# design.net
KiCad netlist of a schematic drawn in Altium Designer
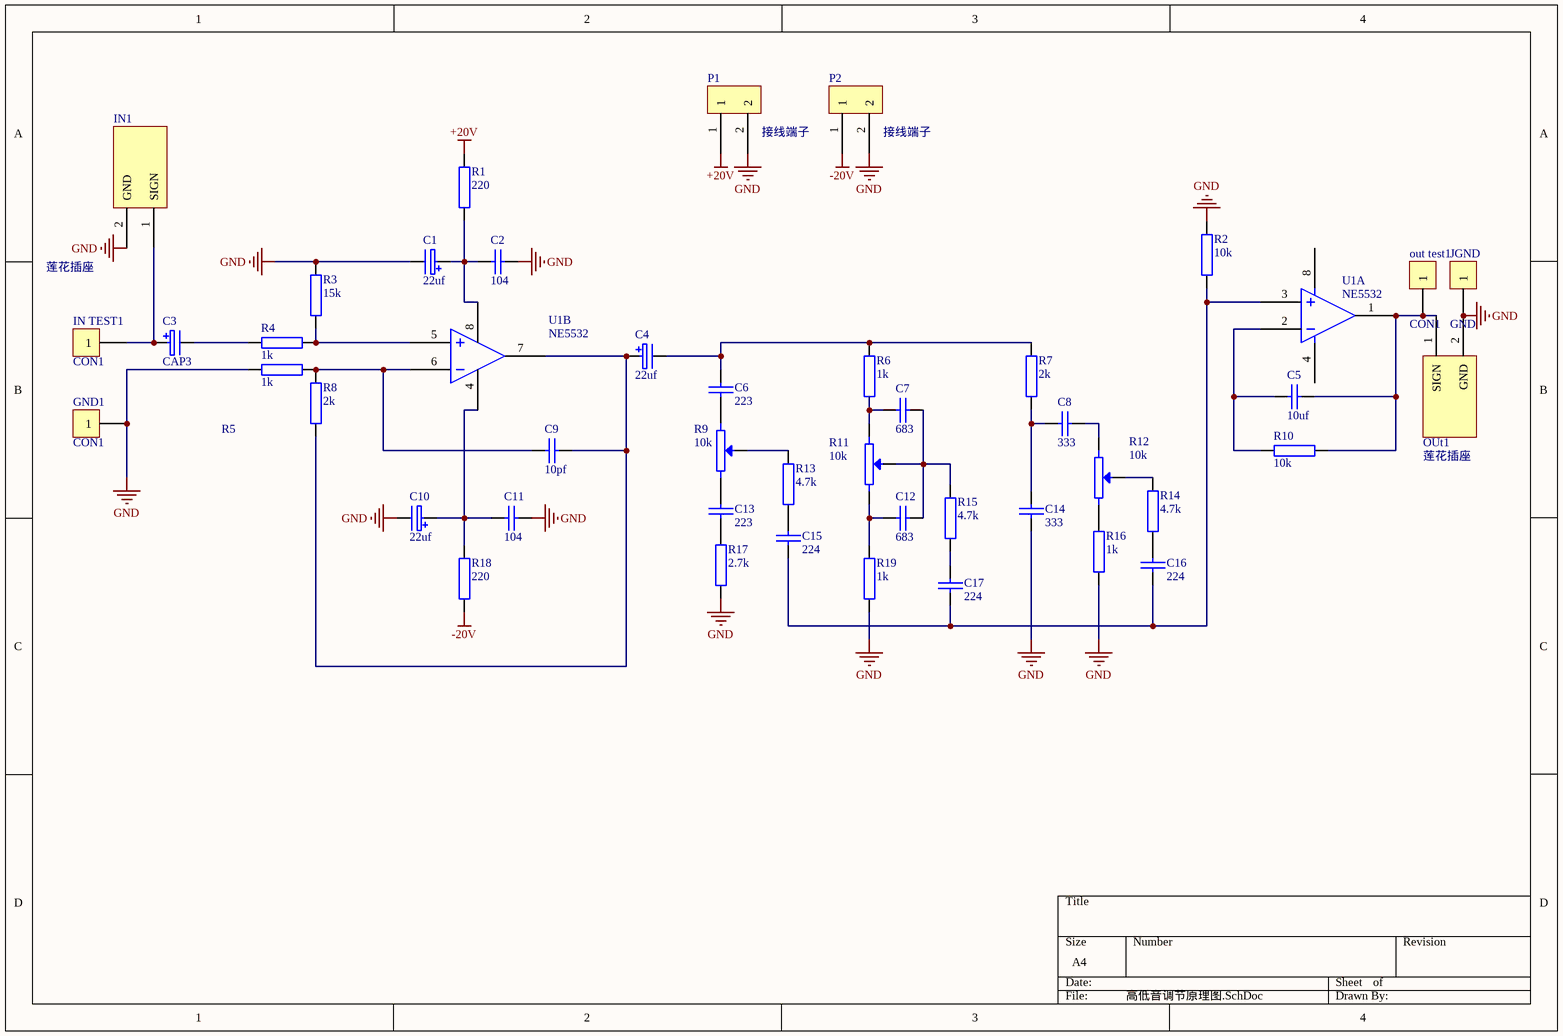
[diagram p0: 高低音调节原理图.SchDoc]

(export (version "E")
  (design (tool "Eeschema 10.0.6"))
  (components
    (comp (ref "C1") (value "22uf") (footprint "CAO2") (libsource (lib "电容") (part "CAP3")))
    (comp (ref "C2") (value "104") (footprint "CAP2") (libsource (lib "电容") (part "CAP1")))
    (comp (ref "C3") (value "CAP3") (footprint "CAO2") (libsource (lib "电容") (part "CAP3")))
    (comp (ref "C4") (value "22uf") (footprint "CAO2") (libsource (lib "电容") (part "CAP3")))
    (comp (ref "C5") (value "10uf") (footprint "CAP2") (libsource (lib "C电容") (part "CAP1")))
    (comp (ref "C6") (value "223") (footprint "CAP2") (libsource (lib "电容") (part "CAP1")))
    (comp (ref "C7") (value "683") (footprint "CAP2") (libsource (lib "电容") (part "CAP1")))
    (comp (ref "C8") (value "333") (footprint "CAP2") (libsource (lib "电容") (part "CAP1")))
    (comp (ref "C9") (value "10pf") (footprint "CAP2") (libsource (lib "电容") (part "CAP1")))
    (comp (ref "C10") (value "22uf") (footprint "CAO2") (libsource (lib "电容") (part "CAP3")))
    (comp (ref "C11") (value "104") (footprint "CAP2") (libsource (lib "电容") (part "CAP1")))
    (comp (ref "C12") (value "683") (footprint "CAP2") (libsource (lib "电容") (part "CAP1")))
    (comp (ref "C13") (value "223") (footprint "CAP2") (libsource (lib "电容") (part "CAP1")))
    (comp (ref "C14") (value "333") (footprint "CAP2") (libsource (lib "电容") (part "CAP1")))
    (comp (ref "C15") (value "224") (footprint "CAP2") (libsource (lib "电容") (part "CAP1")))
    (comp (ref "C16") (value "224") (footprint "CAP2") (libsource (lib "电容") (part "CAP1")))
    (comp (ref "C17") (value "224") (footprint "CAP2") (libsource (lib "电容") (part "CAP1")))
    (comp (ref "GND1")
      (value "CON1")
      (footprint "SIP-1")
      (description "Connector")
      (libsource (lib "排针") (part "CON1"))
    )
    (comp (ref "IN TEST1")
      (value "CON1")
      (footprint "SIP-1")
      (description "Connector")
      (libsource (lib "排针") (part "CON1"))
    )
    (comp (ref "IN1") (value "莲花插座") (footprint "莲花母座") (libsource (lib "音频功放自画库") (part "PCA")))
    (comp (ref "JGND")
      (value "GND")
      (footprint "SIP-1")
      (description "Connector")
      (libsource (lib "") (part "CON1_1"))
    )
    (comp (ref "out test1")
      (value "CON1")
      (footprint "SIP-1")
      (description "Connector")
      (libsource (lib "接口") (part "CON1"))
    )
    (comp (ref "OUt1") (value "莲花插座") (footprint "莲花母座") (libsource (lib "") (part "PCA_1")))
    (comp (ref "P1") (value "接线端子") (footprint "音频功放自画库:接线端子") (libsource (lib "音频功放自画库") (part "接线端子")))
    (comp (ref "P2") (value "接线端子") (footprint "音频功放自画库:接线端子") (libsource (lib "音频功放自画库") (part "接线端子")))
    (comp (ref "R1")
      (value "220")
      (footprint "AXIAL0.4")
      (description "电阻")
      (libsource (lib "电阻") (part "RES"))
    )
    (comp (ref "R2") (value "10k") (footprint "AXIAL0.4") (libsource (lib "R电阻") (part "RES")))
    (comp (ref "R3")
      (value "15k")
      (footprint "AXIAL0.4")
      (description "电阻")
      (libsource (lib "电阻") (part "RES"))
    )
    (comp (ref "R4")
      (value "1k")
      (footprint "AXIAL0.4")
      (description "电阻")
      (libsource (lib "电阻") (part "RES"))
    )
    (comp (ref "R5")
      (value "1k")
      (footprint "AXIAL0.4")
      (description "电阻")
      (libsource (lib "电阻") (part "RES"))
    )
    (comp (ref "R6") (value "1k") (footprint "AXIAL0.4") (libsource (lib "R电阻") (part "RES")))
    (comp (ref "R7") (value "2k") (footprint "AXIAL0.4") (libsource (lib "R电阻") (part "RES")))
    (comp (ref "R8")
      (value "2k")
      (footprint "AXIAL0.4")
      (description "电阻")
      (libsource (lib "电阻") (part "RES"))
    )
    (comp (ref "R9")
      (value "10k")
      (footprint "RVR-A")
      (description "Potentiometer")
      (libsource (lib "R电阻") (part "RPOT-1"))
    )
    (comp (ref "R10") (value "10k") (footprint "AXIAL0.4") (libsource (lib "R电阻") (part "RES")))
    (comp (ref "R11")
      (value "10k")
      (footprint "RVR-A")
      (description "Potentiometer")
      (libsource (lib "R电阻") (part "RPOT-1"))
    )
    (comp (ref "R12")
      (value "10k")
      (footprint "RVR-A")
      (description "Potentiometer")
      (libsource (lib "R电阻") (part "RPOT-1"))
    )
    (comp (ref "R13")
      (value "4.7k")
      (footprint "AXIAL0.4")
      (description "电阻")
      (libsource (lib "电阻") (part "RES"))
    )
    (comp (ref "R14") (value "4.7k") (footprint "AXIAL0.4") (libsource (lib "R电阻") (part "RES")))
    (comp (ref "R15") (value "4.7k") (footprint "AXIAL0.4") (libsource (lib "R电阻") (part "RES")))
    (comp (ref "R16") (value "1k") (footprint "AXIAL0.4") (libsource (lib "R电阻") (part "RES")))
    (comp (ref "R17")
      (value "2.7k")
      (footprint "AXIAL0.4")
      (description "电阻")
      (libsource (lib "电阻") (part "RES"))
    )
    (comp (ref "R18")
      (value "220")
      (footprint "AXIAL0.4")
      (description "电阻")
      (libsource (lib "电阻") (part "RES"))
    )
    (comp (ref "R19")
      (value "1k")
      (footprint "AXIAL0.4")
      (description "电阻")
      (libsource (lib "电阻") (part "RES"))
    )
    (comp (ref "U1") (value "NE5532") (footprint "DIP-8") (libsource (lib "Operational 运放") (part "1458")))
  )
  (nets
    (net (code "1") (name "+20V") (class "Default")
      (node (ref "P1") (pin "1") (pinfunction "1_1") (pintype "passive"))
      (node (ref "R1") (pin "2") (pinfunction "2_2") (pintype "passive"))
    )
    (net (code "2") (name "-20V") (class "Default")
      (node (ref "P2") (pin "1") (pinfunction "1_1") (pintype "passive"))
      (node (ref "R18") (pin "1") (pinfunction "1_1") (pintype "passive"))
    )
    (net (code "3") (name "GND") (class "Default")
      (node (ref "C1") (pin "2") (pintype "passive"))
      (node (ref "C10") (pin "2") (pintype "passive"))
      (node (ref "C11") (pin "1") (pinfunction "1_1") (pintype "passive"))
      (node (ref "C14") (pin "2") (pinfunction "2_2") (pintype "passive"))
      (node (ref "C2") (pin "1") (pinfunction "1_1") (pintype "passive"))
      (node (ref "GND1") (pin "1") (pinfunction "1_1") (pintype "passive"))
      (node (ref "IN1") (pin "2") (pinfunction "GND_2") (pintype "passive"))
      (node (ref "JGND") (pin "1") (pinfunction "1_1") (pintype "passive"))
      (node (ref "OUt1") (pin "2") (pinfunction "GND_2") (pintype "passive"))
      (node (ref "P1") (pin "2") (pinfunction "2_2") (pintype "passive"))
      (node (ref "P2") (pin "2") (pinfunction "2_2") (pintype "passive"))
      (node (ref "R16") (pin "1") (pinfunction "1_1") (pintype "passive"))
      (node (ref "R17") (pin "1") (pinfunction "1_1") (pintype "passive"))
      (node (ref "R19") (pin "1") (pinfunction "1_1") (pintype "passive"))
      (node (ref "R2") (pin "2") (pinfunction "2_2") (pintype "passive"))
      (node (ref "R3") (pin "2") (pinfunction "2_2") (pintype "passive"))
      (node (ref "R5") (pin "1") (pinfunction "1_1") (pintype "passive"))
    )
    (net (code "4") (name "Net-(C1-Pad1)") (class "Default")
      (node (ref "C1") (pin "1") (pintype "passive"))
      (node (ref "C2") (pin "2") (pinfunction "2_2") (pintype "passive"))
      (node (ref "R1") (pin "1") (pinfunction "1_1") (pintype "passive"))
      (node (ref "U1") (pin "8") (pinfunction "8_8") (pintype "passive"))
    )
    (net (code "5") (name "Net-(C3-Pad2)") (class "Default")
      (node (ref "C3") (pin "2") (pintype "passive"))
      (node (ref "R4") (pin "1") (pinfunction "1_1") (pintype "passive"))
    )
    (net (code "6") (name "Net-(C4-Pad1)") (class "Default")
      (node (ref "C4") (pin "1") (pintype "passive"))
      (node (ref "C9") (pin "1") (pinfunction "1_1") (pintype "passive"))
      (node (ref "R8") (pin "1") (pinfunction "1_1") (pintype "passive"))
      (node (ref "U1") (pin "7") (pintype "passive"))
    )
    (net (code "7") (name "Net-(C4-Pad2)") (class "Default")
      (node (ref "C4") (pin "2") (pintype "passive"))
      (node (ref "C6") (pin "1") (pinfunction "1_1") (pintype "passive"))
      (node (ref "R6") (pin "2") (pinfunction "2_2") (pintype "passive"))
      (node (ref "R7") (pin "2") (pinfunction "2_2") (pintype "passive"))
    )
    (net (code "8") (name "Net-(C5-Pad2)") (class "Default")
      (node (ref "C5") (pin "2") (pinfunction "2_2") (pintype "passive"))
      (node (ref "R10") (pin "1") (pinfunction "1_1") (pintype "passive"))
      (node (ref "U1") (pin "2") (pintype "passive"))
    )
    (net (code "9") (name "Net-(C6-Pad2)") (class "Default")
      (node (ref "C6") (pin "2") (pinfunction "2_2") (pintype "passive"))
      (node (ref "R9") (pin "1") (pinfunction "1_1") (pintype "passive"))
    )
    (net (code "10") (name "Net-(C7-Pad2)") (class "Default")
      (node (ref "C7") (pin "2") (pinfunction "2_2") (pintype "passive"))
      (node (ref "R11") (pin "1") (pinfunction "1_1") (pintype "passive"))
      (node (ref "R6") (pin "1") (pinfunction "1_1") (pintype "passive"))
    )
    (net (code "11") (name "Net-(C8-Pad1)") (class "Default")
      (node (ref "C8") (pin "1") (pinfunction "1_1") (pintype "passive"))
      (node (ref "R12") (pin "1") (pinfunction "1_1") (pintype "passive"))
    )
    (net (code "12") (name "Net-(C9-Pad2)") (class "Default")
      (node (ref "C9") (pin "2") (pinfunction "2_2") (pintype "passive"))
      (node (ref "R5") (pin "2") (pinfunction "2_2") (pintype "passive"))
      (node (ref "R8") (pin "2") (pinfunction "2_2") (pintype "passive"))
      (node (ref "U1") (pin "6") (pintype "passive"))
    )
    (net (code "13") (name "Net-(C10-Pad1)") (class "Default")
      (node (ref "C10") (pin "1") (pintype "passive"))
      (node (ref "C11") (pin "2") (pinfunction "2_2") (pintype "passive"))
      (node (ref "R18") (pin "2") (pinfunction "2_2") (pintype "passive"))
      (node (ref "U1") (pin "4") (pinfunction "4_4") (pintype "passive"))
    )
    (net (code "14") (name "Net-(C12-Pad2)") (class "Default")
      (node (ref "C12") (pin "2") (pinfunction "2_2") (pintype "passive"))
      (node (ref "R11") (pin "3") (pinfunction "3_3") (pintype "passive"))
      (node (ref "R19") (pin "2") (pinfunction "2_2") (pintype "passive"))
    )
    (net (code "15") (name "Net-(C13-Pad1)") (class "Default")
      (node (ref "C13") (pin "1") (pinfunction "1_1") (pintype "passive"))
      (node (ref "R9") (pin "3") (pinfunction "3_3") (pintype "passive"))
    )
    (net (code "16") (name "Net-(C13-Pad2)") (class "Default")
      (node (ref "C13") (pin "2") (pinfunction "2_2") (pintype "passive"))
      (node (ref "R17") (pin "2") (pinfunction "2_2") (pintype "passive"))
    )
    (net (code "17") (name "Net-(C14-Pad1)") (class "Default")
      (node (ref "C14") (pin "1") (pinfunction "1_1") (pintype "passive"))
      (node (ref "C8") (pin "2") (pinfunction "2_2") (pintype "passive"))
      (node (ref "R7") (pin "1") (pinfunction "1_1") (pintype "passive"))
    )
    (net (code "18") (name "Net-(C15-Pad1)") (class "Default")
      (node (ref "C15") (pin "1") (pinfunction "1_1") (pintype "passive"))
      (node (ref "R13") (pin "1") (pinfunction "1_1") (pintype "passive"))
    )
    (net (code "19") (name "Net-(C15-Pad2)") (class "Default")
      (node (ref "C15") (pin "2") (pinfunction "2_2") (pintype "passive"))
      (node (ref "C16") (pin "2") (pinfunction "2_2") (pintype "passive"))
      (node (ref "C17") (pin "2") (pinfunction "2_2") (pintype "passive"))
      (node (ref "R2") (pin "1") (pinfunction "1_1") (pintype "passive"))
      (node (ref "U1") (pin "3") (pintype "passive"))
    )
    (net (code "20") (name "Net-(C16-Pad1)") (class "Default")
      (node (ref "C16") (pin "1") (pinfunction "1_1") (pintype "passive"))
      (node (ref "R14") (pin "1") (pinfunction "1_1") (pintype "passive"))
    )
    (net (code "21") (name "Net-(C17-Pad1)") (class "Default")
      (node (ref "C17") (pin "1") (pinfunction "1_1") (pintype "passive"))
      (node (ref "R15") (pin "1") (pinfunction "1_1") (pintype "passive"))
    )
    (net (code "22") (name "Net-(IN1-SIGN)") (class "Default")
      (node (ref "C3") (pin "1") (pintype "passive"))
      (node (ref "IN TEST1") (pin "1") (pinfunction "1_1") (pintype "passive"))
      (node (ref "IN1") (pin "1") (pinfunction "SIGN_1") (pintype "passive"))
    )
    (net (code "23") (name "Net-(OUt1-SIGN)") (class "Default")
      (node (ref "C5") (pin "1") (pinfunction "1_1") (pintype "passive"))
      (node (ref "OUt1") (pin "1") (pinfunction "SIGN_1") (pintype "passive"))
      (node (ref "R10") (pin "2") (pinfunction "2_2") (pintype "passive"))
      (node (ref "U1") (pin "1") (pintype "passive"))
      (node (ref "out test1") (pin "1") (pinfunction "1_1") (pintype "passive"))
    )
    (net (code "24") (name "Net-(R3-Pad1)") (class "Default")
      (node (ref "R3") (pin "1") (pinfunction "1_1") (pintype "passive"))
      (node (ref "R4") (pin "2") (pinfunction "2_2") (pintype "passive"))
      (node (ref "U1") (pin "5") (pintype "passive"))
    )
    (net (code "25") (name "Net-(R9-W)") (class "Default")
      (node (ref "R13") (pin "2") (pinfunction "2_2") (pintype "passive"))
      (node (ref "R9") (pin "2") (pinfunction "W_2") (pintype "passive"))
    )
    (net (code "26") (name "Net-(R11-W)") (class "Default")
      (node (ref "C12") (pin "1") (pinfunction "1_1") (pintype "passive"))
      (node (ref "C7") (pin "1") (pinfunction "1_1") (pintype "passive"))
      (node (ref "R11") (pin "2") (pinfunction "W_2") (pintype "passive"))
      (node (ref "R15") (pin "2") (pinfunction "2_2") (pintype "passive"))
    )
    (net (code "27") (name "Net-(R12-Pad3)") (class "Default")
      (node (ref "R12") (pin "3") (pinfunction "3_3") (pintype "passive"))
      (node (ref "R16") (pin "2") (pinfunction "2_2") (pintype "passive"))
    )
    (net (code "28") (name "Net-(R12-W)") (class "Default")
      (node (ref "R12") (pin "2") (pinfunction "W_2") (pintype "passive"))
      (node (ref "R14") (pin "2") (pinfunction "2_2") (pintype "passive"))
    )
    (net (code "29") (name "unconnected-(U1-Pad4)") (class "Default")
      (node (ref "U1") (pin "4") (pintype "passive"))
    )
    (net (code "30") (name "unconnected-(U1-Pad8)") (class "Default")
      (node (ref "U1") (pin "8") (pintype "passive"))
    )
  )
)
